# BESCape.net
KiCad netlist of a schematic drawn in EAGLE
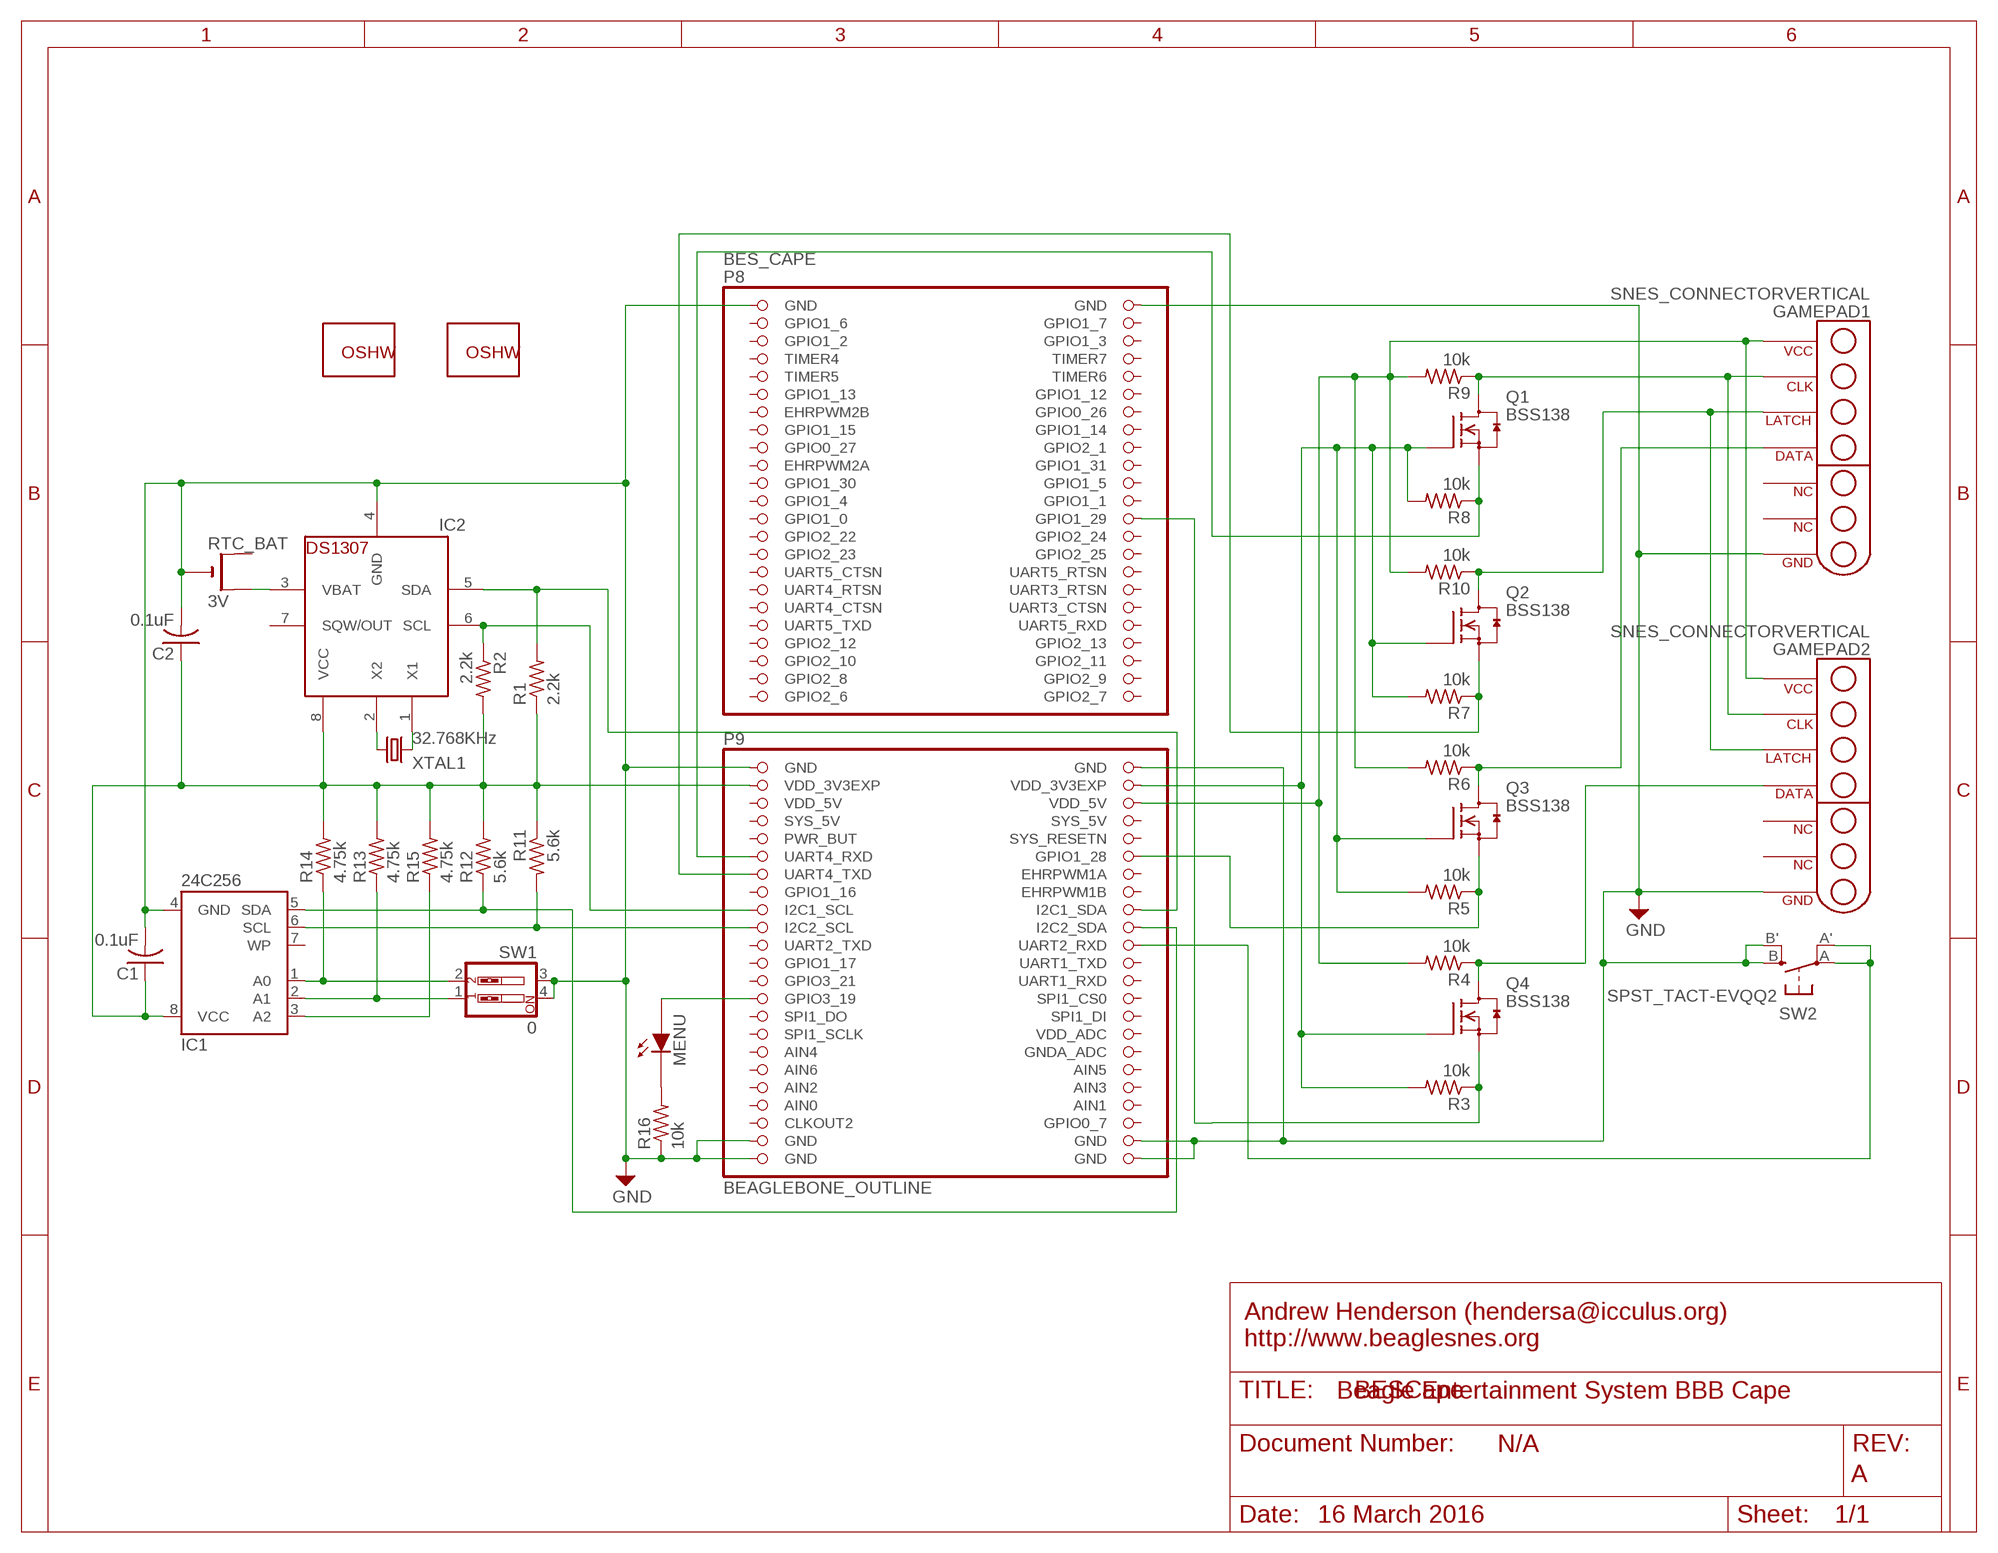
[diagram p0: schematic, sheet 1]

(export (version "E")
  (design (tool "Eeschema 10.0.6"))
  (components
    (comp (ref "BES_CAPE")
      (value "BEAGLEBONE_OUTLINE")
      (footprint "eagle-import:BEAGLEBONE_SHIELD")
      (libsource (lib "eagle-import") (part "BEAGLEBONE_OUTLINE"))
    )
    (comp (ref "C1")
      (value "0.1uF")
      (footprint "eagle-import:C0805")
      (libsource (lib "eagle-import") (part "C-USC0805"))
    )
    (comp (ref "C2")
      (value "0.1uF")
      (footprint "eagle-import:C0805")
      (libsource (lib "eagle-import") (part "C-USC0805"))
    )
    (comp (ref "GAMEPAD1")
      (value "SNES_CONNECTORVERTICAL")
      (footprint "eagle-import:SNES_CONNECTOR_VERTICAL")
      (libsource (lib "eagle-import") (part "SNES_CONNECTORVERTICAL"))
    )
    (comp (ref "GAMEPAD2")
      (value "SNES_CONNECTORVERTICAL")
      (footprint "eagle-import:SNES_CONNECTOR_VERTICAL")
      (libsource (lib "eagle-import") (part "SNES_CONNECTORVERTICAL"))
    )
    (comp (ref "GOLD_ORB_SM1")
      (value "OSHWLOGO_GOLD_ORB_LG")
      (footprint "eagle-import:OSHW0")
      (libsource (lib "eagle-import") (part "OSHWLOGO_GOLD_ORB_LG"))
    )
    (comp (ref "GOLD_ORB_SM3")
      (value "OSHWLOGO_GOLD_ORB_SM")
      (footprint "eagle-import:OSHW2")
      (libsource (lib "eagle-import") (part "OSHWLOGO_GOLD_ORB_SM"))
    )
    (comp (ref "IC1")
      (value "24C256")
      (footprint "eagle-import:DIL08")
      (fields (field (name "MPN") "AT24C1024BW-SH-B"))
      (libsource (lib "eagle-import") (part "AT24CP"))
    )
    (comp (ref "IC2")
      (value "DS1307")
      (footprint "eagle-import:DIL08")
      (libsource (lib "eagle-import") (part "DS1307"))
    )
    (comp (ref "MENU")
      (value "LEDD")
      (footprint "eagle-import:1206P")
      (libsource (lib "eagle-import") (part "LEDD"))
    )
    (comp (ref "Q1")
      (value "BSS138")
      (footprint "eagle-import:SOT23")
      (libsource (lib "eagle-import") (part "BSS138"))
    )
    (comp (ref "Q2")
      (value "BSS138")
      (footprint "eagle-import:SOT23")
      (libsource (lib "eagle-import") (part "BSS138"))
    )
    (comp (ref "Q3")
      (value "BSS138")
      (footprint "eagle-import:SOT23")
      (libsource (lib "eagle-import") (part "BSS138"))
    )
    (comp (ref "Q4")
      (value "BSS138")
      (footprint "eagle-import:SOT23")
      (libsource (lib "eagle-import") (part "BSS138"))
    )
    (comp (ref "R1")
      (value "2.2k")
      (footprint "eagle-import:R0805")
      (libsource (lib "eagle-import") (part "R-US_R0805"))
    )
    (comp (ref "R2")
      (value "2.2k")
      (footprint "eagle-import:R0805")
      (libsource (lib "eagle-import") (part "R-US_R0805"))
    )
    (comp (ref "R3")
      (value "10k")
      (footprint "eagle-import:R0805")
      (libsource (lib "eagle-import") (part "R-US_R0805"))
    )
    (comp (ref "R4")
      (value "10k")
      (footprint "eagle-import:R0805")
      (libsource (lib "eagle-import") (part "R-US_R0805"))
    )
    (comp (ref "R5")
      (value "10k")
      (footprint "eagle-import:R0805")
      (libsource (lib "eagle-import") (part "R-US_R0805"))
    )
    (comp (ref "R6")
      (value "10k")
      (footprint "eagle-import:R0805")
      (libsource (lib "eagle-import") (part "R-US_R0805"))
    )
    (comp (ref "R7")
      (value "10k")
      (footprint "eagle-import:R0805")
      (libsource (lib "eagle-import") (part "R-US_R0805"))
    )
    (comp (ref "R8")
      (value "10k")
      (footprint "eagle-import:R0805")
      (libsource (lib "eagle-import") (part "R-US_R0805"))
    )
    (comp (ref "R9")
      (value "10k")
      (footprint "eagle-import:R0805")
      (libsource (lib "eagle-import") (part "R-US_R0805"))
    )
    (comp (ref "R10")
      (value "10k")
      (footprint "eagle-import:R0805")
      (libsource (lib "eagle-import") (part "R-US_R0805"))
    )
    (comp (ref "R11")
      (value "5.6k")
      (footprint "eagle-import:R0805")
      (libsource (lib "eagle-import") (part "R-US_R0805"))
    )
    (comp (ref "R12")
      (value "5.6k")
      (footprint "eagle-import:R0805")
      (libsource (lib "eagle-import") (part "R-US_R0805"))
    )
    (comp (ref "R13")
      (value "4.75k")
      (footprint "eagle-import:R0805")
      (libsource (lib "eagle-import") (part "R-US_R0805"))
    )
    (comp (ref "R14")
      (value "4.75k")
      (footprint "eagle-import:R0805")
      (libsource (lib "eagle-import") (part "R-US_R0805"))
    )
    (comp (ref "R15")
      (value "4.75k")
      (footprint "eagle-import:R0805")
      (libsource (lib "eagle-import") (part "R-US_R0805"))
    )
    (comp (ref "R16")
      (value "10k")
      (footprint "eagle-import:R0805")
      (libsource (lib "eagle-import") (part "R-US_R0805"))
    )
    (comp (ref "RTC_BAT")
      (value "3V")
      (footprint "eagle-import:CR1220-SMD")
      (libsource (lib "eagle-import") (part "CR1220SMT"))
    )
    (comp (ref "SW1")
      (value "0")
      (footprint "eagle-import:DIPSWITCH-02")
      (libsource (lib "eagle-import") (part "SW_DIP-2"))
    )
    (comp (ref "SW2")
      (value "SPST_TACT-EVQQ2")
      (footprint "eagle-import:EVQ-Q2")
      (libsource (lib "eagle-import") (part "SPST_TACT-EVQQ2"))
    )
    (comp (ref "XTAL1")
      (value "32.768KHz")
      (footprint "eagle-import:TC38H")
      (libsource (lib "eagle-import") (part "CRYSTALTC38H"))
    )
  )
  (nets
    (net (code "1") (name "/AIN0") (class "Default")
      (node (ref "BES_CAPE") (pin "85") (pinfunction "AIN0_85") (pintype "power_in"))
    )
    (net (code "2") (name "/SYS_5V") (class "Default")
      (node (ref "BES_CAPE") (pin "53") (pinfunction "SYS_5V_53") (pintype "power_in"))
    )
    (net (code "3") (name "/VDD_5V") (class "Default")
      (node (ref "BES_CAPE") (pin "51") (pinfunction "VDD_5V_51") (pintype "power_in"))
    )
    (net (code "4") (name "GND") (class "Default")
      (node (ref "BES_CAPE") (pin "1") (pinfunction "GND_1") (pintype "power_in"))
      (node (ref "BES_CAPE") (pin "2") (pinfunction "GND_2") (pintype "power_in"))
      (node (ref "BES_CAPE") (pin "47") (pinfunction "GND_47") (pintype "power_in"))
      (node (ref "BES_CAPE") (pin "48") (pinfunction "GND_48") (pintype "power_in"))
      (node (ref "BES_CAPE") (pin "89") (pinfunction "GND_89") (pintype "power_in"))
      (node (ref "BES_CAPE") (pin "90") (pinfunction "GND_90") (pintype "power_in"))
      (node (ref "BES_CAPE") (pin "91") (pinfunction "GND_91") (pintype "power_in"))
      (node (ref "BES_CAPE") (pin "92") (pinfunction "GND_92") (pintype "power_in"))
      (node (ref "C1") (pin "2") (pinfunction "2_2") (pintype "passive"))
      (node (ref "C2") (pin "2") (pinfunction "2_2") (pintype "passive"))
      (node (ref "GAMEPAD1") (pin "P$17") (pinfunction "GND_P$17") (pintype "passive"))
      (node (ref "GAMEPAD2") (pin "P$17") (pinfunction "GND_P$17") (pintype "passive"))
      (node (ref "IC1") (pin "4") (pinfunction "GND_4") (pintype "power_in"))
      (node (ref "IC2") (pin "4") (pinfunction "GND_4") (pintype "power_in"))
      (node (ref "R16") (pin "1") (pinfunction "1_1") (pintype "passive"))
      (node (ref "RTC_BAT") (pin "-") (pinfunction "-_-") (pintype "passive"))
      (node (ref "SW1") (pin "3") (pinfunction "3_3") (pintype "passive"))
      (node (ref "SW1") (pin "4") (pinfunction "4_4") (pintype "passive"))
      (node (ref "SW2") (pin "B") (pinfunction "S_B") (pintype "passive"))
      (node (ref "SW2") (pin "B'") (pinfunction "S1_B'") (pintype "passive"))
    )
    (net (code "5") (name "Net-(BES_CAPE-GPIO1_28)") (class "Default")
      (node (ref "BES_CAPE") (pin "58") (pinfunction "GPIO1_28_58") (pintype "passive"))
      (node (ref "Q3") (pin "2") (pinfunction "S_2") (pintype "passive"))
      (node (ref "R5") (pin "1") (pinfunction "1_1") (pintype "passive"))
    )
    (net (code "6") (name "Net-(BES_CAPE-GPIO1_29)") (class "Default")
      (node (ref "BES_CAPE") (pin "26") (pinfunction "GPIO1_29_26") (pintype "passive"))
      (node (ref "Q4") (pin "2") (pinfunction "S_2") (pintype "passive"))
      (node (ref "R3") (pin "1") (pinfunction "1_1") (pintype "passive"))
    )
    (net (code "7") (name "Net-(BES_CAPE-GPIO3_19)") (class "Default")
      (node (ref "BES_CAPE") (pin "73") (pinfunction "GPIO3_19_73") (pintype "passive"))
      (node (ref "MENU") (pin "1") (pinfunction "D_IN_1") (pintype "passive"))
    )
    (net (code "8") (name "Net-(BES_CAPE-I2C1_SCL)") (class "Default")
      (node (ref "BES_CAPE") (pin "63") (pinfunction "I2C1_SCL_63") (pintype "passive"))
      (node (ref "IC2") (pin "6") (pinfunction "SCL_6") (pintype "bidirectional"))
      (node (ref "R2") (pin "1") (pinfunction "1_1") (pintype "passive"))
    )
    (net (code "9") (name "Net-(BES_CAPE-I2C1_SDA)") (class "Default")
      (node (ref "BES_CAPE") (pin "64") (pinfunction "I2C1_SDA_64") (pintype "passive"))
      (node (ref "IC2") (pin "5") (pinfunction "SDA_5") (pintype "bidirectional"))
      (node (ref "R1") (pin "2") (pinfunction "2_2") (pintype "passive"))
    )
    (net (code "10") (name "Net-(BES_CAPE-I2C2_SCL)") (class "Default")
      (node (ref "BES_CAPE") (pin "65") (pinfunction "I2C2_SCL_65") (pintype "passive"))
      (node (ref "IC1") (pin "6") (pinfunction "SCL_6") (pintype "bidirectional"))
      (node (ref "R11") (pin "2") (pinfunction "2_2") (pintype "passive"))
    )
    (net (code "11") (name "Net-(BES_CAPE-I2C2_SDA)") (class "Default")
      (node (ref "BES_CAPE") (pin "66") (pinfunction "I2C2_SDA_66") (pintype "passive"))
      (node (ref "IC1") (pin "5") (pinfunction "SDA_5") (pintype "bidirectional"))
      (node (ref "R12") (pin "1") (pinfunction "1_1") (pintype "passive"))
    )
    (net (code "12") (name "Net-(BES_CAPE-UART2_RXD)") (class "Default")
      (node (ref "BES_CAPE") (pin "68") (pinfunction "UART2_RXD_68") (pintype "passive"))
      (node (ref "SW2") (pin "A") (pinfunction "P_A") (pintype "passive"))
      (node (ref "SW2") (pin "A'") (pinfunction "P1_A'") (pintype "passive"))
    )
    (net (code "13") (name "Net-(BES_CAPE-UART4_RXD)") (class "Default")
      (node (ref "BES_CAPE") (pin "57") (pinfunction "UART4_RXD_57") (pintype "passive"))
      (node (ref "Q1") (pin "2") (pinfunction "S_2") (pintype "passive"))
      (node (ref "R8") (pin "1") (pinfunction "1_1") (pintype "passive"))
    )
    (net (code "14") (name "Net-(BES_CAPE-UART4_TXD)") (class "Default")
      (node (ref "BES_CAPE") (pin "59") (pinfunction "UART4_TXD_59") (pintype "passive"))
      (node (ref "Q2") (pin "2") (pinfunction "S_2") (pintype "passive"))
      (node (ref "R7") (pin "1") (pinfunction "1_1") (pintype "passive"))
    )
    (net (code "15") (name "Net-(GAMEPAD1-CLK)") (class "Default")
      (node (ref "GAMEPAD1") (pin "P$12") (pinfunction "CLK_P$12") (pintype "input"))
      (node (ref "GAMEPAD2") (pin "P$12") (pinfunction "CLK_P$12") (pintype "input"))
      (node (ref "Q1") (pin "3") (pinfunction "D_3") (pintype "passive"))
      (node (ref "R9") (pin "1") (pinfunction "1_1") (pintype "passive"))
    )
    (net (code "16") (name "Net-(GAMEPAD1-DATA)") (class "Default")
      (node (ref "GAMEPAD1") (pin "P$14") (pinfunction "DATA_P$14") (pintype "output"))
      (node (ref "Q3") (pin "3") (pinfunction "D_3") (pintype "passive"))
      (node (ref "R6") (pin "1") (pinfunction "1_1") (pintype "passive"))
    )
    (net (code "17") (name "Net-(GAMEPAD1-LATCH)") (class "Default")
      (node (ref "GAMEPAD1") (pin "P$13") (pinfunction "LATCH_P$13") (pintype "input"))
      (node (ref "GAMEPAD2") (pin "P$13") (pinfunction "LATCH_P$13") (pintype "input"))
      (node (ref "Q2") (pin "3") (pinfunction "D_3") (pintype "passive"))
      (node (ref "R10") (pin "1") (pinfunction "1_1") (pintype "passive"))
    )
    (net (code "18") (name "Net-(GAMEPAD1-VCC)") (class "Default")
      (node (ref "BES_CAPE") (pin "52") (pinfunction "VDD_5V_52") (pintype "power_in"))
      (node (ref "GAMEPAD1") (pin "P$11") (pinfunction "VCC_P$11") (pintype "power_in"))
      (node (ref "GAMEPAD2") (pin "P$11") (pinfunction "VCC_P$11") (pintype "power_in"))
      (node (ref "R10") (pin "2") (pinfunction "2_2") (pintype "passive"))
      (node (ref "R4") (pin "2") (pinfunction "2_2") (pintype "passive"))
      (node (ref "R6") (pin "2") (pinfunction "2_2") (pintype "passive"))
      (node (ref "R9") (pin "2") (pinfunction "2_2") (pintype "passive"))
    )
    (net (code "19") (name "Net-(GAMEPAD2-DATA)") (class "Default")
      (node (ref "GAMEPAD2") (pin "P$14") (pinfunction "DATA_P$14") (pintype "output"))
      (node (ref "Q4") (pin "3") (pinfunction "D_3") (pintype "passive"))
      (node (ref "R4") (pin "1") (pinfunction "1_1") (pintype "passive"))
    )
    (net (code "20") (name "Net-(IC1-A0)") (class "Default")
      (node (ref "IC1") (pin "1") (pinfunction "A0_1") (pintype "input"))
      (node (ref "R14") (pin "1") (pinfunction "1_1") (pintype "passive"))
      (node (ref "SW1") (pin "2") (pinfunction "2_2") (pintype "passive"))
    )
    (net (code "21") (name "Net-(IC1-A1)") (class "Default")
      (node (ref "IC1") (pin "2") (pinfunction "A1_2") (pintype "input"))
      (node (ref "R13") (pin "1") (pinfunction "1_1") (pintype "passive"))
      (node (ref "SW1") (pin "1") (pinfunction "1_1") (pintype "passive"))
    )
    (net (code "22") (name "Net-(IC1-A2)") (class "Default")
      (node (ref "IC1") (pin "3") (pinfunction "A2_3") (pintype "input"))
      (node (ref "R15") (pin "1") (pinfunction "1_1") (pintype "passive"))
    )
    (net (code "23") (name "Net-(IC1-VCC)") (class "Default")
      (node (ref "BES_CAPE") (pin "49") (pinfunction "VDD_3V3EXP_49") (pintype "power_in"))
      (node (ref "C1") (pin "1") (pinfunction "1_1") (pintype "passive"))
      (node (ref "C2") (pin "1") (pinfunction "1_1") (pintype "passive"))
      (node (ref "IC1") (pin "8") (pinfunction "VCC_8") (pintype "power_in"))
      (node (ref "IC2") (pin "8") (pinfunction "VCC_8") (pintype "power_in"))
      (node (ref "R1") (pin "1") (pinfunction "1_1") (pintype "passive"))
      (node (ref "R11") (pin "1") (pinfunction "1_1") (pintype "passive"))
      (node (ref "R12") (pin "2") (pinfunction "2_2") (pintype "passive"))
      (node (ref "R13") (pin "2") (pinfunction "2_2") (pintype "passive"))
      (node (ref "R14") (pin "2") (pinfunction "2_2") (pintype "passive"))
      (node (ref "R15") (pin "2") (pinfunction "2_2") (pintype "passive"))
      (node (ref "R2") (pin "2") (pinfunction "2_2") (pintype "passive"))
    )
    (net (code "24") (name "Net-(IC2-VBAT)") (class "Default")
      (node (ref "IC2") (pin "3") (pinfunction "VBAT_3") (pintype "power_in"))
      (node (ref "RTC_BAT") (pin "+$2") (pinfunction "+1_+$2") (pintype "passive"))
    )
    (net (code "25") (name "Net-(IC2-X1)") (class "Default")
      (node (ref "IC2") (pin "1") (pinfunction "X1_1") (pintype "passive"))
      (node (ref "XTAL1") (pin "2") (pinfunction "2_2") (pintype "passive"))
    )
    (net (code "26") (name "Net-(IC2-X2)") (class "Default")
      (node (ref "IC2") (pin "2") (pinfunction "X2_2") (pintype "passive"))
      (node (ref "XTAL1") (pin "1") (pinfunction "1_1") (pintype "passive"))
    )
    (net (code "27") (name "Net-(MENU-D_OUT)") (class "Default")
      (node (ref "MENU") (pin "2") (pinfunction "D_OUT_2") (pintype "passive"))
      (node (ref "R16") (pin "2") (pinfunction "2_2") (pintype "passive"))
    )
    (net (code "28") (name "Net-(Q1-G)") (class "Default")
      (node (ref "BES_CAPE") (pin "50") (pinfunction "VDD_3V3EXP_50") (pintype "power_in"))
      (node (ref "Q1") (pin "1") (pinfunction "G_1") (pintype "passive"))
      (node (ref "Q2") (pin "1") (pinfunction "G_1") (pintype "passive"))
      (node (ref "Q3") (pin "1") (pinfunction "G_1") (pintype "passive"))
      (node (ref "Q4") (pin "1") (pinfunction "G_1") (pintype "passive"))
      (node (ref "R3") (pin "2") (pinfunction "2_2") (pintype "passive"))
      (node (ref "R5") (pin "2") (pinfunction "2_2") (pintype "passive"))
      (node (ref "R7") (pin "2") (pinfunction "2_2") (pintype "passive"))
      (node (ref "R8") (pin "2") (pinfunction "2_2") (pintype "passive"))
    )
    (net (code "29") (name "unconnected-(BES_CAPE-AIN1-Pad86)") (class "Default")
      (node (ref "BES_CAPE") (pin "86") (pinfunction "AIN1_86") (pintype "passive"))
    )
    (net (code "30") (name "unconnected-(BES_CAPE-AIN2-Pad83)") (class "Default")
      (node (ref "BES_CAPE") (pin "83") (pinfunction "AIN2_83") (pintype "passive"))
    )
    (net (code "31") (name "unconnected-(BES_CAPE-AIN3-Pad84)") (class "Default")
      (node (ref "BES_CAPE") (pin "84") (pinfunction "AIN3_84") (pintype "passive"))
    )
    (net (code "32") (name "unconnected-(BES_CAPE-AIN4-Pad79)") (class "Default")
      (node (ref "BES_CAPE") (pin "79") (pinfunction "AIN4_79") (pintype "passive"))
    )
    (net (code "33") (name "unconnected-(BES_CAPE-AIN5-Pad82)") (class "Default")
      (node (ref "BES_CAPE") (pin "82") (pinfunction "AIN5_82") (pintype "passive"))
    )
    (net (code "34") (name "unconnected-(BES_CAPE-AIN6-Pad81)") (class "Default")
      (node (ref "BES_CAPE") (pin "81") (pinfunction "AIN6_81") (pintype "passive"))
    )
    (net (code "35") (name "unconnected-(BES_CAPE-CLKOUT2-Pad87)") (class "Default")
      (node (ref "BES_CAPE") (pin "87") (pinfunction "CLKOUT2_87") (pintype "input"))
    )
    (net (code "36") (name "unconnected-(BES_CAPE-EHRPWM1A-Pad60)") (class "Default")
      (node (ref "BES_CAPE") (pin "60") (pinfunction "EHRPWM1A_60") (pintype "passive"))
    )
    (net (code "37") (name "unconnected-(BES_CAPE-EHRPWM1B-Pad62)") (class "Default")
      (node (ref "BES_CAPE") (pin "62") (pinfunction "EHRPWM1B_62") (pintype "passive"))
    )
    (net (code "38") (name "unconnected-(BES_CAPE-EHRPWM2A-Pad19)") (class "Default")
      (node (ref "BES_CAPE") (pin "19") (pinfunction "EHRPWM2A_19") (pintype "passive"))
    )
    (net (code "39") (name "unconnected-(BES_CAPE-EHRPWM2B-Pad13)") (class "Default")
      (node (ref "BES_CAPE") (pin "13") (pinfunction "EHRPWM2B_13") (pintype "passive"))
    )
    (net (code "40") (name "unconnected-(BES_CAPE-GNDA_ADC-Pad80)") (class "Default")
      (node (ref "BES_CAPE") (pin "80") (pinfunction "GNDA_ADC_80") (pintype "passive"))
    )
    (net (code "41") (name "unconnected-(BES_CAPE-GPIO0_7-Pad88)") (class "Default")
      (node (ref "BES_CAPE") (pin "88") (pinfunction "GPIO0_7_88") (pintype "passive"))
    )
    (net (code "42") (name "unconnected-(BES_CAPE-GPIO0_26-Pad14)") (class "Default")
      (node (ref "BES_CAPE") (pin "14") (pinfunction "GPIO0_26_14") (pintype "passive"))
    )
    (net (code "43") (name "unconnected-(BES_CAPE-GPIO0_27-Pad17)") (class "Default")
      (node (ref "BES_CAPE") (pin "17") (pinfunction "GPIO0_27_17") (pintype "passive"))
    )
    (net (code "44") (name "unconnected-(BES_CAPE-GPIO1_0-Pad25)") (class "Default")
      (node (ref "BES_CAPE") (pin "25") (pinfunction "GPIO1_0_25") (pintype "passive"))
    )
    (net (code "45") (name "unconnected-(BES_CAPE-GPIO1_1-Pad24)") (class "Default")
      (node (ref "BES_CAPE") (pin "24") (pinfunction "GPIO1_1_24") (pintype "passive"))
    )
    (net (code "46") (name "unconnected-(BES_CAPE-GPIO1_2-Pad5)") (class "Default")
      (node (ref "BES_CAPE") (pin "5") (pinfunction "GPIO1_2_5") (pintype "passive"))
    )
    (net (code "47") (name "unconnected-(BES_CAPE-GPIO1_3-Pad6)") (class "Default")
      (node (ref "BES_CAPE") (pin "6") (pinfunction "GPIO1_3_6") (pintype "passive"))
    )
    (net (code "48") (name "unconnected-(BES_CAPE-GPIO1_4-Pad23)") (class "Default")
      (node (ref "BES_CAPE") (pin "23") (pinfunction "GPIO1_4_23") (pintype "passive"))
    )
    (net (code "49") (name "unconnected-(BES_CAPE-GPIO1_5-Pad22)") (class "Default")
      (node (ref "BES_CAPE") (pin "22") (pinfunction "GPIO1_5_22") (pintype "passive"))
    )
    (net (code "50") (name "unconnected-(BES_CAPE-GPIO1_6-Pad3)") (class "Default")
      (node (ref "BES_CAPE") (pin "3") (pinfunction "GPIO1_6_3") (pintype "passive"))
    )
    (net (code "51") (name "unconnected-(BES_CAPE-GPIO1_7-Pad4)") (class "Default")
      (node (ref "BES_CAPE") (pin "4") (pinfunction "GPIO1_7_4") (pintype "passive"))
    )
    (net (code "52") (name "unconnected-(BES_CAPE-GPIO1_12-Pad12)") (class "Default")
      (node (ref "BES_CAPE") (pin "12") (pinfunction "GPIO1_12_12") (pintype "passive"))
    )
    (net (code "53") (name "unconnected-(BES_CAPE-GPIO1_13-Pad11)") (class "Default")
      (node (ref "BES_CAPE") (pin "11") (pinfunction "GPIO1_13_11") (pintype "passive"))
    )
    (net (code "54") (name "unconnected-(BES_CAPE-GPIO1_14-Pad16)") (class "Default")
      (node (ref "BES_CAPE") (pin "16") (pinfunction "GPIO1_14_16") (pintype "passive"))
    )
    (net (code "55") (name "unconnected-(BES_CAPE-GPIO1_15-Pad15)") (class "Default")
      (node (ref "BES_CAPE") (pin "15") (pinfunction "GPIO1_15_15") (pintype "passive"))
    )
    (net (code "56") (name "unconnected-(BES_CAPE-GPIO1_16-Pad61)") (class "Default")
      (node (ref "BES_CAPE") (pin "61") (pinfunction "GPIO1_16_61") (pintype "passive"))
    )
    (net (code "57") (name "unconnected-(BES_CAPE-GPIO1_17-Pad69)") (class "Default")
      (node (ref "BES_CAPE") (pin "69") (pinfunction "GPIO1_17_69") (pintype "passive"))
    )
    (net (code "58") (name "unconnected-(BES_CAPE-GPIO1_30-Pad21)") (class "Default")
      (node (ref "BES_CAPE") (pin "21") (pinfunction "GPIO1_30_21") (pintype "passive"))
    )
    (net (code "59") (name "unconnected-(BES_CAPE-GPIO1_31-Pad20)") (class "Default")
      (node (ref "BES_CAPE") (pin "20") (pinfunction "GPIO1_31_20") (pintype "passive"))
    )
    (net (code "60") (name "unconnected-(BES_CAPE-GPIO2_1-Pad18)") (class "Default")
      (node (ref "BES_CAPE") (pin "18") (pinfunction "GPIO2_1_18") (pintype "passive"))
    )
    (net (code "61") (name "unconnected-(BES_CAPE-GPIO2_6-Pad45)") (class "Default")
      (node (ref "BES_CAPE") (pin "45") (pinfunction "GPIO2_6_45") (pintype "passive"))
    )
    (net (code "62") (name "unconnected-(BES_CAPE-GPIO2_7-Pad46)") (class "Default")
      (node (ref "BES_CAPE") (pin "46") (pinfunction "GPIO2_7_46") (pintype "passive"))
    )
    (net (code "63") (name "unconnected-(BES_CAPE-GPIO2_8-Pad43)") (class "Default")
      (node (ref "BES_CAPE") (pin "43") (pinfunction "GPIO2_8_43") (pintype "passive"))
    )
    (net (code "64") (name "unconnected-(BES_CAPE-GPIO2_9-Pad44)") (class "Default")
      (node (ref "BES_CAPE") (pin "44") (pinfunction "GPIO2_9_44") (pintype "passive"))
    )
    (net (code "65") (name "unconnected-(BES_CAPE-GPIO2_10-Pad41)") (class "Default")
      (node (ref "BES_CAPE") (pin "41") (pinfunction "GPIO2_10_41") (pintype "passive"))
    )
    (net (code "66") (name "unconnected-(BES_CAPE-GPIO2_11-Pad42)") (class "Default")
      (node (ref "BES_CAPE") (pin "42") (pinfunction "GPIO2_11_42") (pintype "passive"))
    )
    (net (code "67") (name "unconnected-(BES_CAPE-GPIO2_12-Pad39)") (class "Default")
      (node (ref "BES_CAPE") (pin "39") (pinfunction "GPIO2_12_39") (pintype "passive"))
    )
    (net (code "68") (name "unconnected-(BES_CAPE-GPIO2_13-Pad40)") (class "Default")
      (node (ref "BES_CAPE") (pin "40") (pinfunction "GPIO2_13_40") (pintype "passive"))
    )
    (net (code "69") (name "unconnected-(BES_CAPE-GPIO2_22-Pad27)") (class "Default")
      (node (ref "BES_CAPE") (pin "27") (pinfunction "GPIO2_22_27") (pintype "passive"))
    )
    (net (code "70") (name "unconnected-(BES_CAPE-GPIO2_23-Pad29)") (class "Default")
      (node (ref "BES_CAPE") (pin "29") (pinfunction "GPIO2_23_29") (pintype "passive"))
    )
    (net (code "71") (name "unconnected-(BES_CAPE-GPIO2_24-Pad28)") (class "Default")
      (node (ref "BES_CAPE") (pin "28") (pinfunction "GPIO2_24_28") (pintype "passive"))
    )
    (net (code "72") (name "unconnected-(BES_CAPE-GPIO2_25-Pad30)") (class "Default")
      (node (ref "BES_CAPE") (pin "30") (pinfunction "GPIO2_25_30") (pintype "passive"))
    )
    (net (code "73") (name "unconnected-(BES_CAPE-GPIO3_21-Pad71)") (class "Default")
      (node (ref "BES_CAPE") (pin "71") (pinfunction "GPIO3_21_71") (pintype "passive"))
    )
    (net (code "74") (name "unconnected-(BES_CAPE-PWR_BUT-Pad55)") (class "Default")
      (node (ref "BES_CAPE") (pin "55") (pinfunction "PWR_BUT_55") (pintype "passive"))
    )
    (net (code "75") (name "unconnected-(BES_CAPE-SPI1_CS0-Pad74)") (class "Default")
      (node (ref "BES_CAPE") (pin "74") (pinfunction "SPI1_CS0_74") (pintype "passive"))
    )
    (net (code "76") (name "unconnected-(BES_CAPE-SPI1_DI-Pad76)") (class "Default")
      (node (ref "BES_CAPE") (pin "76") (pinfunction "SPI1_DI_76") (pintype "passive"))
    )
    (net (code "77") (name "unconnected-(BES_CAPE-SPI1_DO-Pad75)") (class "Default")
      (node (ref "BES_CAPE") (pin "75") (pinfunction "SPI1_DO_75") (pintype "passive"))
    )
    (net (code "78") (name "unconnected-(BES_CAPE-SPI1_SCLK-Pad77)") (class "Default")
      (node (ref "BES_CAPE") (pin "77") (pinfunction "SPI1_SCLK_77") (pintype "passive"))
    )
    (net (code "79") (name "unconnected-(BES_CAPE-SYS_5V-Pad54)") (class "Default")
      (node (ref "BES_CAPE") (pin "54") (pinfunction "SYS_5V_54") (pintype "passive"))
    )
    (net (code "80") (name "unconnected-(BES_CAPE-SYS_RESETN-Pad56)") (class "Default")
      (node (ref "BES_CAPE") (pin "56") (pinfunction "SYS_RESETN_56") (pintype "passive"))
    )
    (net (code "81") (name "unconnected-(BES_CAPE-TIMER4-Pad7)") (class "Default")
      (node (ref "BES_CAPE") (pin "7") (pinfunction "TIMER4_7") (pintype "passive"))
    )
    (net (code "82") (name "unconnected-(BES_CAPE-TIMER5-Pad9)") (class "Default")
      (node (ref "BES_CAPE") (pin "9") (pinfunction "TIMER5_9") (pintype "passive"))
    )
    (net (code "83") (name "unconnected-(BES_CAPE-TIMER6-Pad10)") (class "Default")
      (node (ref "BES_CAPE") (pin "10") (pinfunction "TIMER6_10") (pintype "passive"))
    )
    (net (code "84") (name "unconnected-(BES_CAPE-TIMER7-Pad8)") (class "Default")
      (node (ref "BES_CAPE") (pin "8") (pinfunction "TIMER7_8") (pintype "passive"))
    )
    (net (code "85") (name "unconnected-(BES_CAPE-UART1_RXD-Pad72)") (class "Default")
      (node (ref "BES_CAPE") (pin "72") (pinfunction "UART1_RXD_72") (pintype "passive"))
    )
    (net (code "86") (name "unconnected-(BES_CAPE-UART1_TXD-Pad70)") (class "Default")
      (node (ref "BES_CAPE") (pin "70") (pinfunction "UART1_TXD_70") (pintype "passive"))
    )
    (net (code "87") (name "unconnected-(BES_CAPE-UART2_TXD-Pad67)") (class "Default")
      (node (ref "BES_CAPE") (pin "67") (pinfunction "UART2_TXD_67") (pintype "passive"))
    )
    (net (code "88") (name "unconnected-(BES_CAPE-UART3_CTSN-Pad36)") (class "Default")
      (node (ref "BES_CAPE") (pin "36") (pinfunction "UART3_CTSN_36") (pintype "passive"))
    )
    (net (code "89") (name "unconnected-(BES_CAPE-UART3_RTSN-Pad34)") (class "Default")
      (node (ref "BES_CAPE") (pin "34") (pinfunction "UART3_RTSN_34") (pintype "passive"))
    )
    (net (code "90") (name "unconnected-(BES_CAPE-UART4_CTSN-Pad35)") (class "Default")
      (node (ref "BES_CAPE") (pin "35") (pinfunction "UART4_CTSN_35") (pintype "passive"))
    )
    (net (code "91") (name "unconnected-(BES_CAPE-UART4_RTSN-Pad33)") (class "Default")
      (node (ref "BES_CAPE") (pin "33") (pinfunction "UART4_RTSN_33") (pintype "passive"))
    )
    (net (code "92") (name "unconnected-(BES_CAPE-UART5_CTSN-Pad31)") (class "Default")
      (node (ref "BES_CAPE") (pin "31") (pinfunction "UART5_CTSN_31") (pintype "passive"))
    )
    (net (code "93") (name "unconnected-(BES_CAPE-UART5_RTSN-Pad32)") (class "Default")
      (node (ref "BES_CAPE") (pin "32") (pinfunction "UART5_RTSN_32") (pintype "passive"))
    )
    (net (code "94") (name "unconnected-(BES_CAPE-UART5_RXD-Pad38)") (class "Default")
      (node (ref "BES_CAPE") (pin "38") (pinfunction "UART5_RXD_38") (pintype "passive"))
    )
    (net (code "95") (name "unconnected-(BES_CAPE-UART5_TXD-Pad37)") (class "Default")
      (node (ref "BES_CAPE") (pin "37") (pinfunction "UART5_TXD_37") (pintype "passive"))
    )
    (net (code "96") (name "unconnected-(BES_CAPE-VDD_ADC-Pad78)") (class "Default")
      (node (ref "BES_CAPE") (pin "78") (pinfunction "VDD_ADC_78") (pintype "passive"))
    )
    (net (code "97") (name "unconnected-(GAMEPAD1-NC1-PadP$15)") (class "Default")
      (node (ref "GAMEPAD1") (pin "P$15") (pinfunction "NC1_P$15") (pintype "no_connect"))
    )
    (net (code "98") (name "unconnected-(GAMEPAD1-NC2-PadP$16)") (class "Default")
      (node (ref "GAMEPAD1") (pin "P$16") (pinfunction "NC2_P$16") (pintype "no_connect"))
    )
    (net (code "99") (name "unconnected-(GAMEPAD2-NC1-PadP$15)") (class "Default")
      (node (ref "GAMEPAD2") (pin "P$15") (pinfunction "NC1_P$15") (pintype "no_connect"))
    )
    (net (code "100") (name "unconnected-(GAMEPAD2-NC2-PadP$16)") (class "Default")
      (node (ref "GAMEPAD2") (pin "P$16") (pinfunction "NC2_P$16") (pintype "no_connect"))
    )
    (net (code "101") (name "unconnected-(IC1-WP-Pad7)") (class "Default")
      (node (ref "IC1") (pin "7") (pinfunction "WP_7") (pintype "input"))
    )
    (net (code "102") (name "unconnected-(IC2-SQW{slash}OUT-Pad7)") (class "Default")
      (node (ref "IC2") (pin "7") (pinfunction "SQW/OUT_7") (pintype "bidirectional"))
    )
    (net (code "103") (name "unconnected-(RTC_BAT-+-Pad+$1)") (class "Default")
      (node (ref "RTC_BAT") (pin "+$1") (pinfunction "+_+$1") (pintype "passive"))
    )
  )
)
